# G1000_Dual_Encoder_Base.net
KiCad netlist of a schematic drawn in EasyEDA
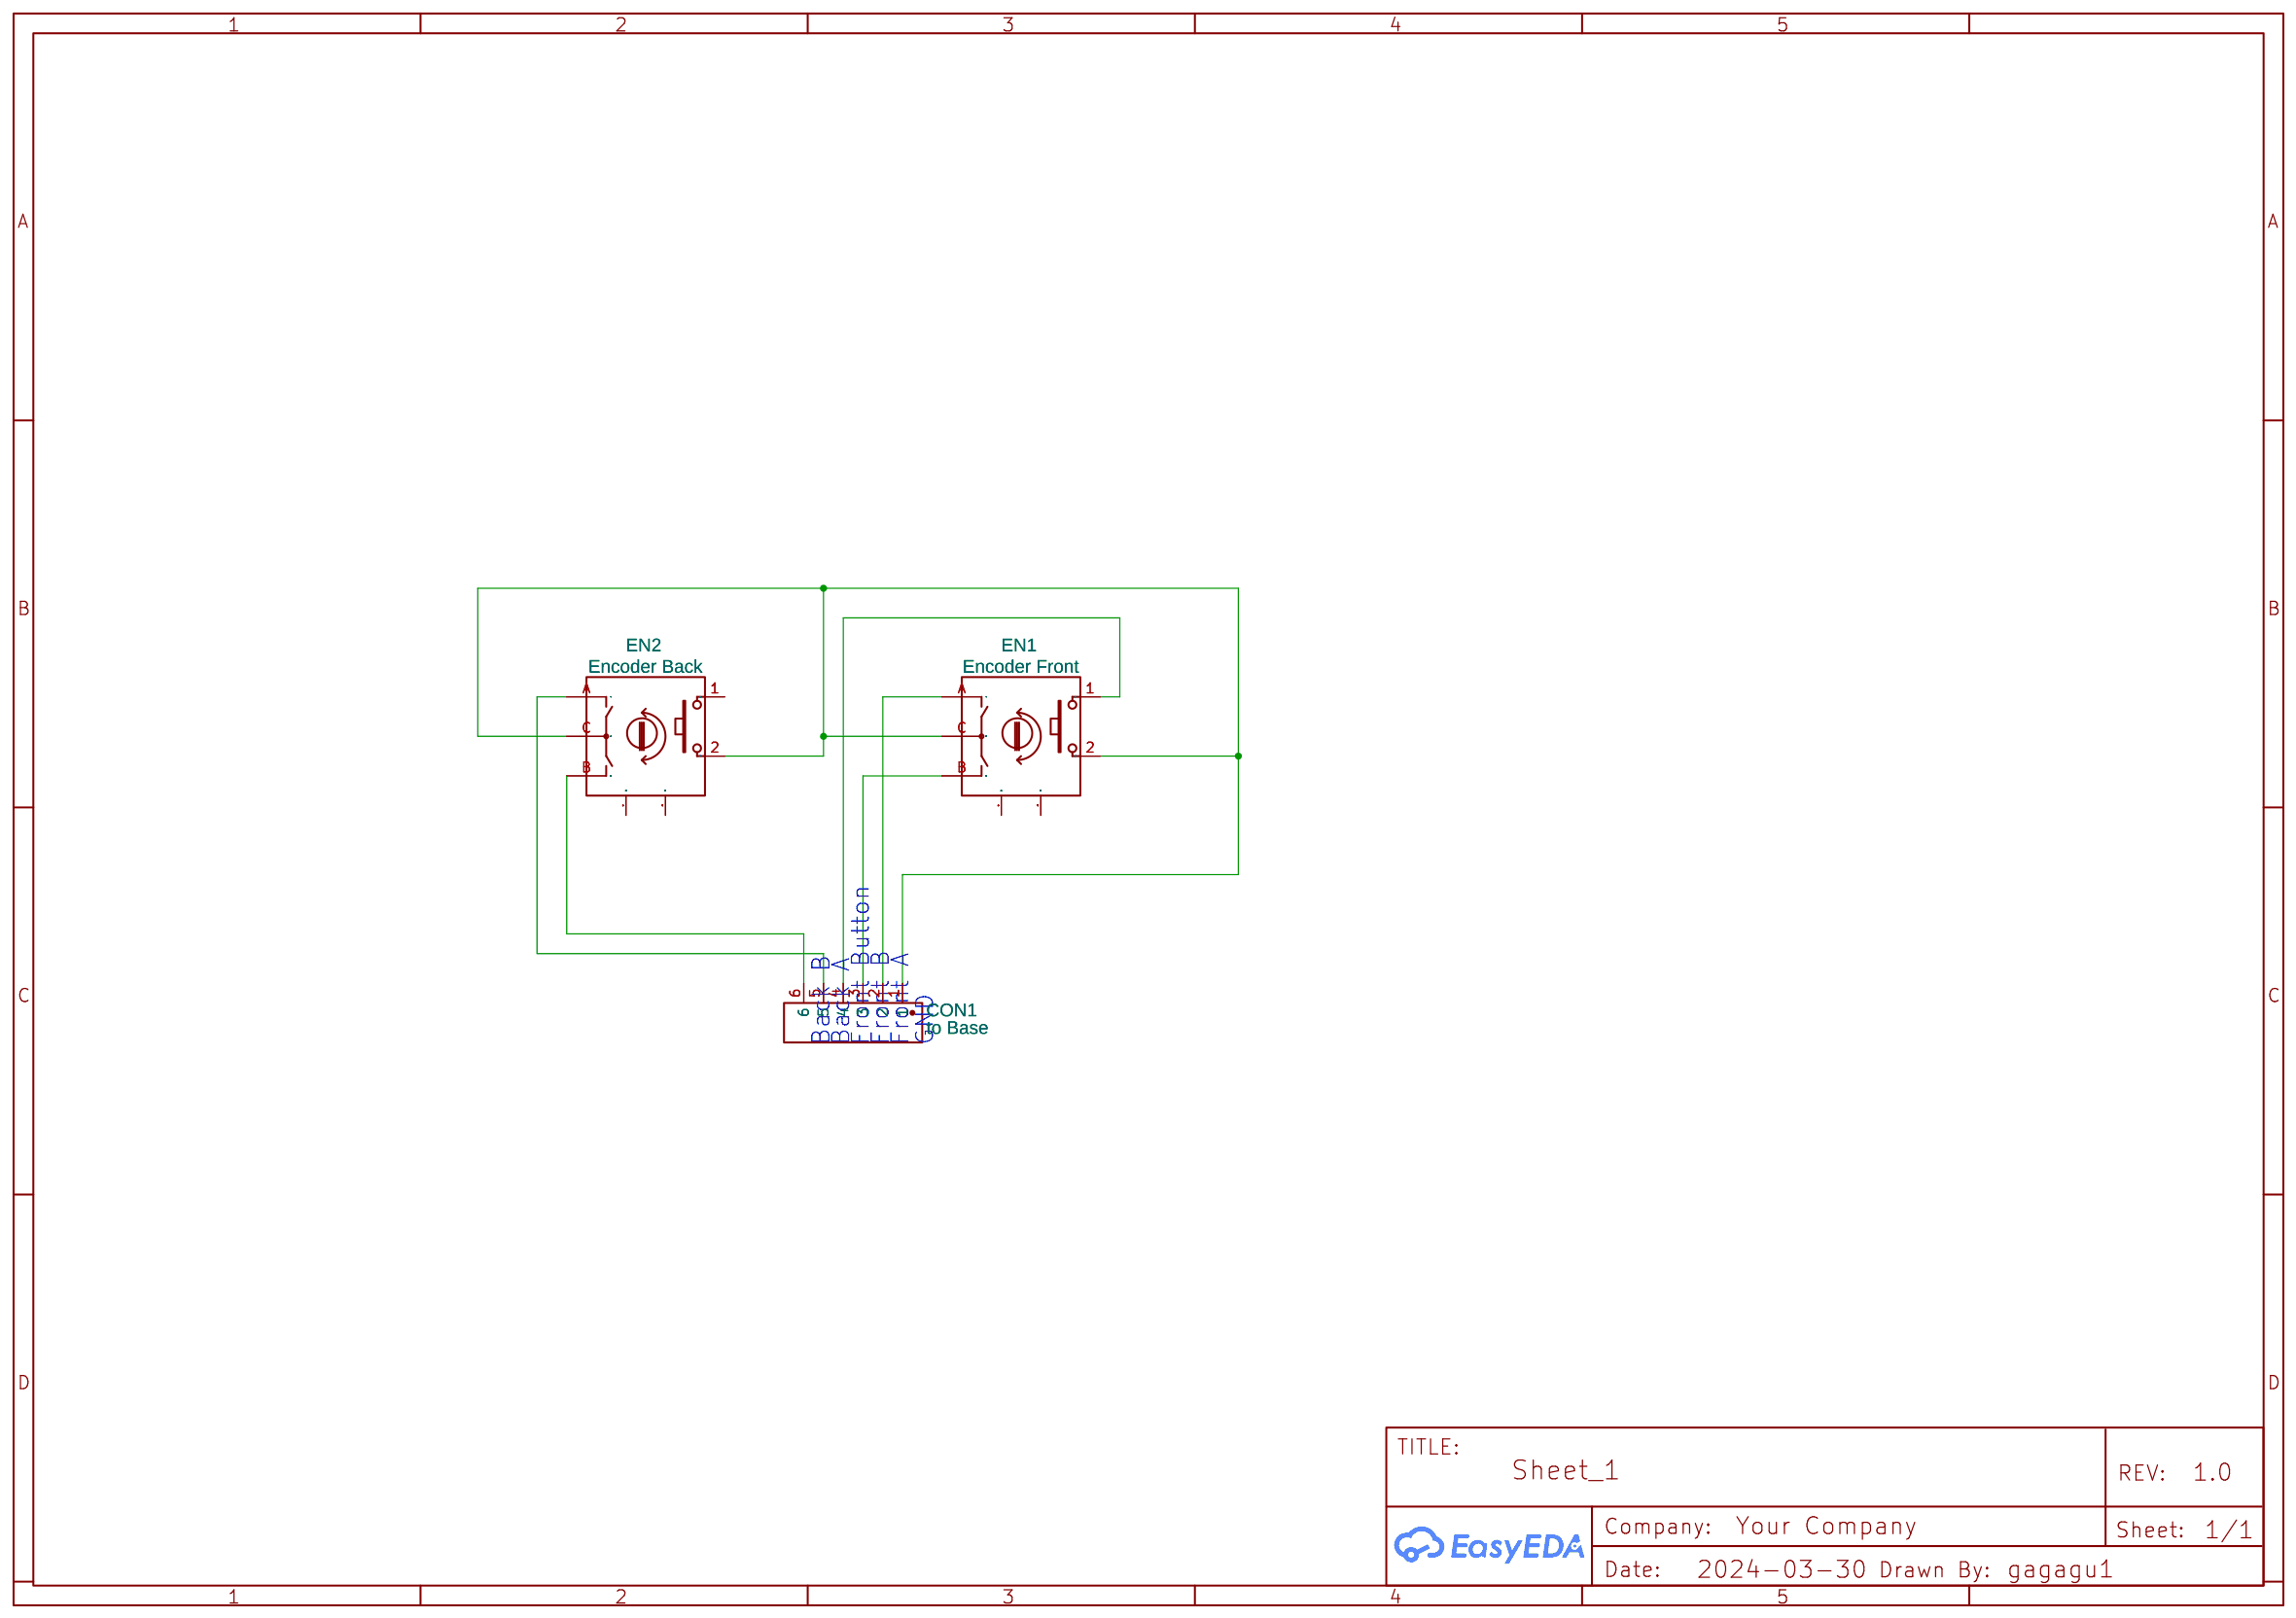
[diagram p0: schematic sheet]

(export (version "E")
  (design (tool "Eeschema 10.0.6"))
  (components
    (comp (ref "CON1")
      (value "to Base")
      (fields (field (name "Manufacturer Part") "XH-6A") (field (name "Manufacturer") "CAX"))
      (libsource (lib "") (part "ARUN-CONN-TH_XH-6A"))
    )
    (comp (ref "EN1")
      (value "Encoder Front")
      (fields (field (name "Manufacturer Part") "PEC11R-4015F-S0024") (field (name "Manufacturer") "BOURNS"))
      (libsource (lib "") (part "PEC11R-4015F-S0024"))
    )
    (comp (ref "EN2")
      (value "Encoder Back")
      (fields (field (name "Manufacturer Part") "PEC11R-4015F-S0024") (field (name "Manufacturer") "BOURNS"))
      (libsource (lib "") (part "PEC11R-4015F-S0024"))
    )
  )
  (nets
    (net (code "1") (name "Net-(CON1-Pad1)") (class "Default")
      (node (ref "CON1") (pin "1") (pinfunction "1_1") (pintype "unspecified"))
      (node (ref "EN1") (pin "2") (pinfunction "2_2") (pintype "unspecified"))
      (node (ref "EN1") (pin "C") (pinfunction "C_C") (pintype "unspecified"))
      (node (ref "EN2") (pin "2") (pinfunction "2_2") (pintype "unspecified"))
      (node (ref "EN2") (pin "C") (pinfunction "C_C") (pintype "unspecified"))
    )
    (net (code "2") (name "Net-(CON1-Pad2)") (class "Default")
      (node (ref "CON1") (pin "2") (pinfunction "2_2") (pintype "unspecified"))
      (node (ref "EN1") (pin "A") (pinfunction "A_A") (pintype "unspecified"))
    )
    (net (code "3") (name "Net-(CON1-Pad3)") (class "Default")
      (node (ref "CON1") (pin "3") (pinfunction "3_3") (pintype "unspecified"))
      (node (ref "EN1") (pin "B") (pinfunction "B_B") (pintype "unspecified"))
    )
    (net (code "4") (name "Net-(CON1-Pad4)") (class "Default")
      (node (ref "CON1") (pin "4") (pinfunction "4_4") (pintype "unspecified"))
      (node (ref "EN1") (pin "1") (pinfunction "1_1") (pintype "unspecified"))
    )
    (net (code "5") (name "Net-(CON1-Pad5)") (class "Default")
      (node (ref "CON1") (pin "5") (pinfunction "5_5") (pintype "unspecified"))
      (node (ref "EN2") (pin "A") (pinfunction "A_A") (pintype "unspecified"))
    )
    (net (code "6") (name "Net-(CON1-Pad6)") (class "Default")
      (node (ref "CON1") (pin "6") (pinfunction "6_6") (pintype "unspecified"))
      (node (ref "EN2") (pin "B") (pinfunction "B_B") (pintype "unspecified"))
    )
    (net (code "7") (name "unconnected-(EN1-PadMT1)") (class "Default")
      (node (ref "EN1") (pin "MT1") (pinfunction "MT1_MT1") (pintype "unspecified"))
    )
    (net (code "8") (name "unconnected-(EN1-PadMT2)") (class "Default")
      (node (ref "EN1") (pin "MT2") (pinfunction "MT2_MT2") (pintype "unspecified"))
    )
    (net (code "9") (name "unconnected-(EN2-Pad1)") (class "Default")
      (node (ref "EN2") (pin "1") (pinfunction "1_1") (pintype "unspecified"))
    )
    (net (code "10") (name "unconnected-(EN2-PadMT1)") (class "Default")
      (node (ref "EN2") (pin "MT1") (pinfunction "MT1_MT1") (pintype "unspecified"))
    )
    (net (code "11") (name "unconnected-(EN2-PadMT2)") (class "Default")
      (node (ref "EN2") (pin "MT2") (pinfunction "MT2_MT2") (pintype "unspecified"))
    )
  )
)
